# LED_Tweezer.net
KiCad netlist of a schematic drawn in Altium Designer
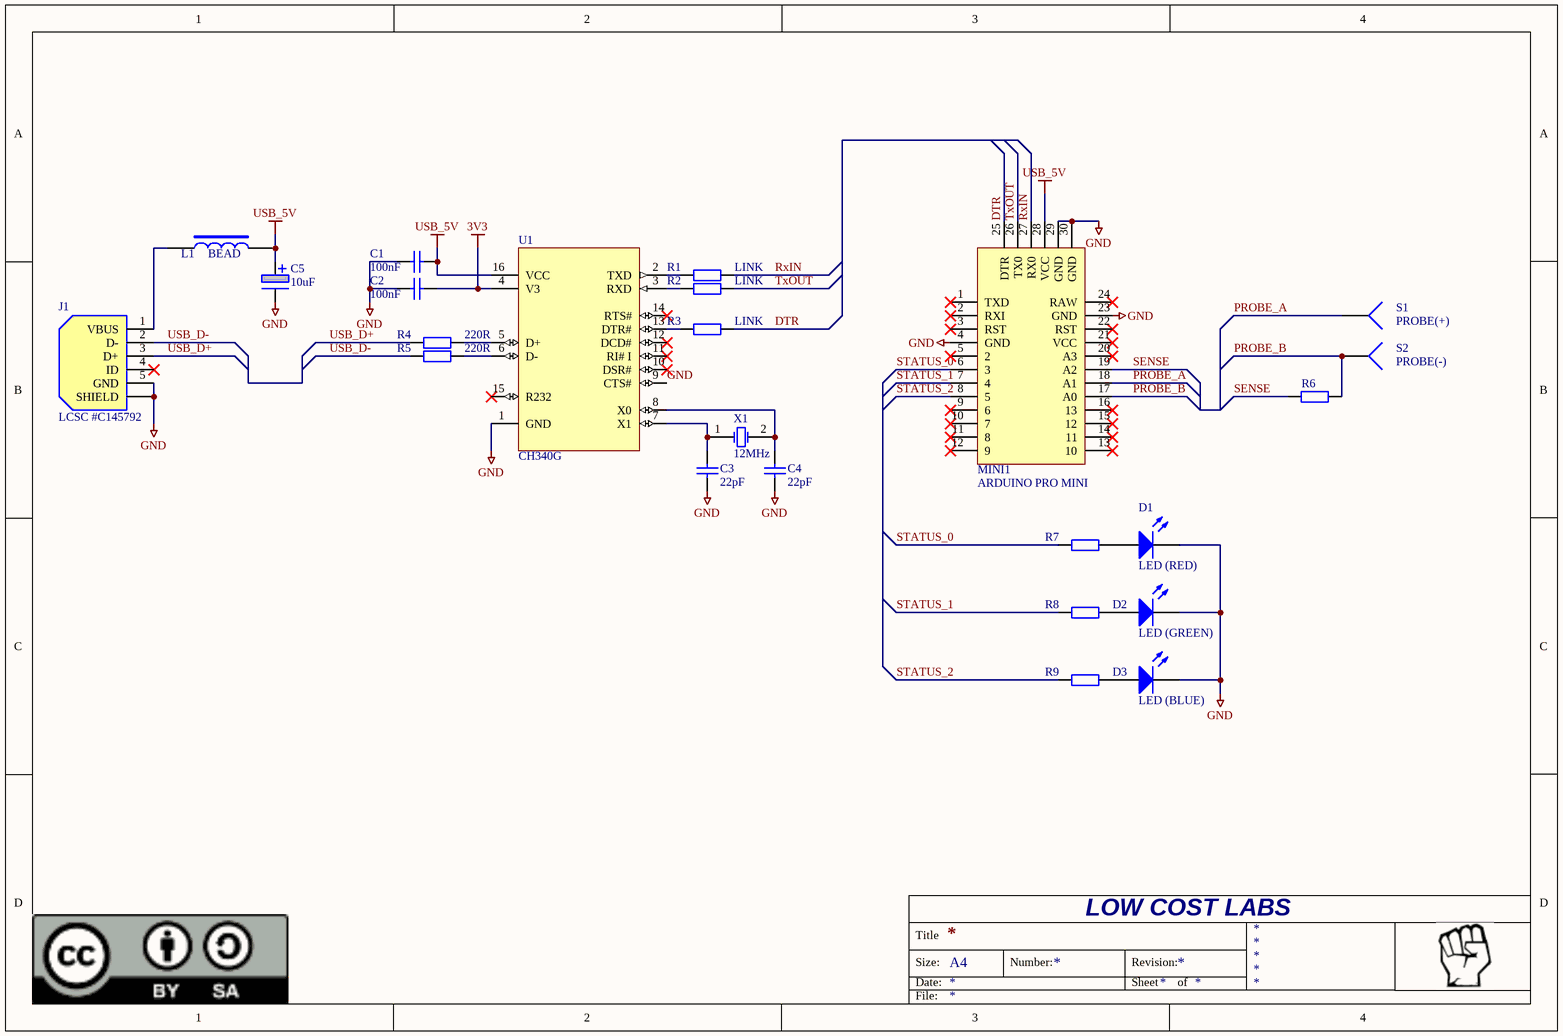
[diagram p0: LED Tweezer.SchDoc]

(export (version "E")
  (design (tool "Eeschema 10.0.6"))
  (components
    (comp (ref "C1")
      (value "100nF")
      (footprint "CAPACITOR 0805")
      (description "GENERIC 0603 CAPACITOR (IPCC COMPLIANT)")
      (libsource (lib "FavoritesLibrary") (part "SYM-xz5e0ntg24ede4ywr789-1"))
    )
    (comp (ref "C2")
      (value "100nF")
      (footprint "CAPACITOR 0805")
      (description "GENERIC 0603 CAPACITOR (IPCC COMPLIANT)")
      (libsource (lib "FavoritesLibrary") (part "SYM-xz5e0ntg24ede4ywr789-1"))
    )
    (comp (ref "C3")
      (value "22pF")
      (footprint "CAPACITOR 0805")
      (description "Capacitor 0805")
      (libsource (lib "altium-import") (part "root_3_SYM-xz5e0ntg24ede4ywr789-1_"))
    )
    (comp (ref "C4")
      (value "22pF")
      (footprint "CAPACITOR 0805")
      (description "Capacitor 0805")
      (libsource (lib "altium-import") (part "root_3_SYM-xz5e0ntg24ede4ywr789-1_"))
    )
    (comp (ref "C5")
      (value "10uF")
      (footprint "Simon Says:CAP ELECTRO 5mm")
      (description "5mm Through Hole Electrolytic 2mm Pitch, 5mm height")
      (libsource (lib "FavoritesLibrary") (part "SYM-su2zmkw1kc3z49ns9isd-1"))
    )
    (comp (ref "D1")
      (value "LED (RED)")
      (footprint "LED(3D) 3MM VERTICAL (GREEN)")
      (description "3mm RED LED")
      (fields (field (name "MOUSER PART NO.") "604-WP132XIT") (field (name "FARNELL PART NO.") "1003393"))
      (libsource (lib "NASCO") (part "LED 3mm RED"))
    )
    (comp (ref "D2")
      (value "LED (GREEN)")
      (footprint "LED(3D) 3MM VERTICAL (GREEN)")
      (description "3mm RED LED")
      (fields (field (name "MOUSER PART NO.") "604-WP132XIT") (field (name "FARNELL PART NO.") "1003393"))
      (libsource (lib "NASCO") (part "LED 3mm RED"))
    )
    (comp (ref "D3")
      (value "LED (BLUE)")
      (footprint "LED(3D) 3MM VERTICAL (GREEN)")
      (description "3mm RED LED")
      (fields (field (name "MOUSER PART NO.") "604-WP132XIT") (field (name "FARNELL PART NO.") "1003393"))
      (libsource (lib "NASCO") (part "LED 3mm RED"))
    )
    (comp (ref "J1")
      (value "LCSC #C145792")
      (footprint "MICRO-B-USB-SMD")
      (description "Hirose ZX62D-B-5PA8 MICRO USB")
      (fields (field (name "MANUFACTURER PART NUMBER") "ZX62D-B-5PA8"))
      (libsource (lib "altium-import") (part "root_0_HIRO-ZX62D-B_"))
    )
    (comp (ref "L1")
      (value "BEAD")
      (footprint "RES (3D) - 1210")
      (description "INDUCTOR SMD 1210")
      (fields (field (name "MOUSER PART NO.") "636-2512063007Y3") (field (name "MANUFACTURER") "Fair-Rite"))
      (libsource (lib "NASCO") (part "INDUCTOR SMD 1210 100uH"))
    )
    (comp (ref "MINI1")
      (value "ARDUINO PRO MINI")
      (footprint "ARDUINO PRO MINI")
      (libsource (lib "EletroSketch") (part "ARDUINO PRO MINI"))
    )
    (comp (ref "R1")
      (value "LINK")
      (footprint "RESISTOR 0805")
      (description "GENERIC 0603 RESISTOR (IPCC COMPLIANT)")
      (libsource (lib "altium-import") (part "root_0_SYM-nyzt47j077kuntqddeld-1_"))
    )
    (comp (ref "R2")
      (value "LINK")
      (footprint "RESISTOR 0805")
      (description "GENERIC 0603 RESISTOR (IPCC COMPLIANT)")
      (libsource (lib "altium-import") (part "root_0_SYM-nyzt47j077kuntqddeld-1_"))
    )
    (comp (ref "R3")
      (value "LINK")
      (footprint "RESISTOR 0805")
      (description "GENERIC 0603 RESISTOR (IPCC COMPLIANT)")
      (libsource (lib "altium-import") (part "root_0_SYM-nyzt47j077kuntqddeld-1_"))
    )
    (comp (ref "R4")
      (value "220R")
      (footprint "RESISTOR 0805")
      (description "GENERIC 0603 RESISTOR (IPCC COMPLIANT)")
      (libsource (lib "altium-import") (part "root_0_SYM-nyzt47j077kuntqddeld-1_"))
    )
    (comp (ref "R5")
      (value "220R")
      (footprint "RESISTOR 0805")
      (description "GENERIC 0603 RESISTOR (IPCC COMPLIANT)")
      (libsource (lib "altium-import") (part "root_0_SYM-nyzt47j077kuntqddeld-1_"))
    )
    (comp (ref "R6")
      (value "~")
      (footprint "RESISTOR 0805")
      (description "Resistor")
      (fields (field (name "PUBLISHER") "Altium Limited"))
      (libsource (lib "Miscellaneous Devices") (part "Res2"))
    )
    (comp (ref "R7")
      (value "~")
      (footprint "RESISTOR 0805")
      (description "Resistor")
      (fields (field (name "PUBLISHER") "Altium Limited"))
      (libsource (lib "Miscellaneous Devices") (part "Res2"))
    )
    (comp (ref "R8")
      (value "~")
      (footprint "RESISTOR 0805")
      (description "Resistor")
      (fields (field (name "PUBLISHER") "Altium Limited"))
      (libsource (lib "Miscellaneous Devices") (part "Res2"))
    )
    (comp (ref "R9")
      (value "~")
      (footprint "RESISTOR 0805")
      (description "Resistor")
      (fields (field (name "PUBLISHER") "Altium Limited"))
      (libsource (lib "") (part "Res2_1"))
    )
    (comp (ref "S1")
      (value "PROBE(+)")
      (footprint "SOCKET-SQUARE")
      (description "Banana Socket")
      (libsource (lib "Schlib1") (part "Banana Plug Socket"))
    )
    (comp (ref "S2")
      (value "PROBE(-)")
      (footprint "SOCKET-ROUND")
      (description "Banana Socket")
      (libsource (lib "Schlib1") (part "Banana Plug Socket"))
    )
    (comp (ref "U1")
      (value "CH340G")
      (footprint "SOIC-16")
      (description "CH340G USB To Serial (TTL) Module")
      (libsource (lib "Schlib1") (part "CH340G"))
    )
    (comp (ref "X1")
      (value "12MHz")
      (footprint "ABRA-AB15T-2_V")
      (libsource (lib "altium-import") (part "root_0_ABRA-XTAL_1-2-2_"))
    )
  )
  (nets
    (net (code "1") (name "/DTR") (class "Default")
      (node (ref "MINI1") (pin "25") (pinfunction "DTR_25") (pintype "passive"))
      (node (ref "R3") (pin "2") (pinfunction "2_2") (pintype "passive"))
    )
    (net (code "2") (name "/PROBE_A") (class "Default")
      (node (ref "MINI1") (pin "18") (pinfunction "A1_18") (pintype "passive"))
      (node (ref "S1") (pin "1") (pinfunction "1_1") (pintype "passive"))
    )
    (net (code "3") (name "/PROBE_B") (class "Default")
      (node (ref "MINI1") (pin "17") (pinfunction "A0_17") (pintype "passive"))
      (node (ref "R6") (pin "2") (pinfunction "2_2") (pintype "passive"))
      (node (ref "S2") (pin "1") (pinfunction "1_1") (pintype "passive"))
    )
    (net (code "4") (name "/RxIN") (class "Default")
      (node (ref "MINI1") (pin "27") (pinfunction "RX0_27") (pintype "passive"))
      (node (ref "R1") (pin "2") (pinfunction "2_2") (pintype "passive"))
    )
    (net (code "5") (name "/SENSE") (class "Default")
      (node (ref "MINI1") (pin "19") (pinfunction "A2_19") (pintype "passive"))
      (node (ref "R6") (pin "1") (pinfunction "1_1") (pintype "passive"))
    )
    (net (code "6") (name "/STATUS_0") (class "Default")
      (node (ref "MINI1") (pin "6") (pinfunction "3_6") (pintype "passive"))
      (node (ref "R7") (pin "1") (pinfunction "1_1") (pintype "passive"))
    )
    (net (code "7") (name "/STATUS_1") (class "Default")
      (node (ref "MINI1") (pin "7") (pinfunction "4_7") (pintype "passive"))
      (node (ref "R8") (pin "1") (pinfunction "1_1") (pintype "passive"))
    )
    (net (code "8") (name "/STATUS_2") (class "Default")
      (node (ref "MINI1") (pin "8") (pinfunction "5_8") (pintype "passive"))
      (node (ref "R9") (pin "2") (pinfunction "2_2") (pintype "passive"))
    )
    (net (code "9") (name "/TxOUT") (class "Default")
      (node (ref "MINI1") (pin "26") (pinfunction "TX0_26") (pintype "passive"))
      (node (ref "R2") (pin "2") (pinfunction "2_2") (pintype "passive"))
    )
    (net (code "10") (name "/USB_D+") (class "Default")
      (node (ref "J1") (pin "3") (pinfunction "D+_3") (pintype "passive"))
      (node (ref "R4") (pin "1") (pinfunction "1_1") (pintype "passive"))
    )
    (net (code "11") (name "/USB_D-") (class "Default")
      (node (ref "J1") (pin "2") (pinfunction "D-_2") (pintype "passive"))
      (node (ref "R5") (pin "1") (pinfunction "1_1") (pintype "passive"))
    )
    (net (code "12") (name "3V3") (class "Default")
      (node (ref "C2") (pin "1") (pinfunction "1_1") (pintype "passive"))
      (node (ref "U1") (pin "4") (pinfunction "V3_4") (pintype "power_in"))
    )
    (net (code "13") (name "GND") (class "Default")
      (node (ref "C1") (pin "2") (pinfunction "2_2") (pintype "passive"))
      (node (ref "C2") (pin "2") (pinfunction "2_2") (pintype "passive"))
      (node (ref "C3") (pin "2") (pinfunction "2_2") (pintype "passive"))
      (node (ref "C4") (pin "2") (pinfunction "2_2") (pintype "passive"))
      (node (ref "C5") (pin "2") (pinfunction "2_2") (pintype "passive"))
      (node (ref "D1") (pin "2") (pinfunction "K_2") (pintype "passive"))
      (node (ref "D2") (pin "2") (pinfunction "K_2") (pintype "passive"))
      (node (ref "D3") (pin "2") (pinfunction "K_2") (pintype "passive"))
      (node (ref "J1") (pin "5") (pinfunction "GND_5") (pintype "passive"))
      (node (ref "J1") (pin "SHIELD") (pinfunction "SHIELD_SHIELD") (pintype "passive"))
      (node (ref "MINI1") (pin "23") (pinfunction "GND_23") (pintype "passive"))
      (node (ref "MINI1") (pin "29") (pinfunction "GND_29") (pintype "passive"))
      (node (ref "MINI1") (pin "30") (pinfunction "GND_30") (pintype "passive"))
      (node (ref "MINI1") (pin "4") (pinfunction "GND_4") (pintype "passive"))
      (node (ref "U1") (pin "1") (pinfunction "GND_1") (pintype "power_in"))
      (node (ref "U1") (pin "9") (pinfunction "CTS#_9") (pintype "bidirectional"))
    )
    (net (code "14") (name "Net-(D1-A)") (class "Default")
      (node (ref "D1") (pin "1") (pinfunction "A_1") (pintype "passive"))
      (node (ref "R7") (pin "2") (pinfunction "2_2") (pintype "passive"))
    )
    (net (code "15") (name "Net-(D2-A)") (class "Default")
      (node (ref "D2") (pin "1") (pinfunction "A_1") (pintype "passive"))
      (node (ref "R8") (pin "2") (pinfunction "2_2") (pintype "passive"))
    )
    (net (code "16") (name "Net-(D3-A)") (class "Default")
      (node (ref "D3") (pin "1") (pinfunction "A_1") (pintype "passive"))
      (node (ref "R9") (pin "1") (pinfunction "1_1") (pintype "passive"))
    )
    (net (code "17") (name "Net-(J1-VBUS)") (class "Default")
      (node (ref "J1") (pin "1") (pinfunction "VBUS_1") (pintype "passive"))
      (node (ref "L1") (pin "1") (pinfunction "1_1") (pintype "passive"))
    )
    (net (code "18") (name "Net-(U1-D+)") (class "Default")
      (node (ref "R4") (pin "2") (pinfunction "2_2") (pintype "passive"))
      (node (ref "U1") (pin "5") (pinfunction "D+_5") (pintype "bidirectional"))
    )
    (net (code "19") (name "Net-(U1-D-)") (class "Default")
      (node (ref "R5") (pin "2") (pinfunction "2_2") (pintype "passive"))
      (node (ref "U1") (pin "6") (pinfunction "D-_6") (pintype "bidirectional"))
    )
    (net (code "20") (name "Net-(U1-DTR#)") (class "Default")
      (node (ref "R3") (pin "1") (pinfunction "1_1") (pintype "passive"))
      (node (ref "U1") (pin "13") (pinfunction "DTR#_13") (pintype "bidirectional"))
    )
    (net (code "21") (name "Net-(U1-RXD)") (class "Default")
      (node (ref "R2") (pin "1") (pinfunction "1_1") (pintype "passive"))
      (node (ref "U1") (pin "3") (pinfunction "RXD_3") (pintype "input"))
    )
    (net (code "22") (name "Net-(U1-TXD)") (class "Default")
      (node (ref "R1") (pin "1") (pinfunction "1_1") (pintype "passive"))
      (node (ref "U1") (pin "2") (pinfunction "TXD_2") (pintype "output"))
    )
    (net (code "23") (name "Net-(U1-X0)") (class "Default")
      (node (ref "C4") (pin "1") (pinfunction "1_1") (pintype "passive"))
      (node (ref "U1") (pin "8") (pinfunction "X0_8") (pintype "bidirectional"))
      (node (ref "X1") (pin "2") (pinfunction "X2_2") (pintype "passive"))
    )
    (net (code "24") (name "Net-(U1-X1)") (class "Default")
      (node (ref "C3") (pin "1") (pinfunction "1_1") (pintype "passive"))
      (node (ref "U1") (pin "7") (pinfunction "X1_7") (pintype "bidirectional"))
      (node (ref "X1") (pin "1") (pinfunction "X1_1") (pintype "passive"))
    )
    (net (code "25") (name "USB_5V") (class "Default")
      (node (ref "C1") (pin "1") (pinfunction "1_1") (pintype "passive"))
      (node (ref "C5") (pin "1") (pinfunction "1_1") (pintype "passive"))
      (node (ref "L1") (pin "2") (pinfunction "2_2") (pintype "passive"))
      (node (ref "MINI1") (pin "28") (pinfunction "VCC_28") (pintype "passive"))
      (node (ref "U1") (pin "16") (pinfunction "VCC_16") (pintype "power_in"))
    )
    (net (code "26") (name "unconnected-(J1-ID-Pad4)") (class "Default")
      (node (ref "J1") (pin "4") (pinfunction "ID_4") (pintype "passive+no_connect"))
    )
    (net (code "27") (name "unconnected-(MINI1-2-Pad5)") (class "Default")
      (node (ref "MINI1") (pin "5") (pinfunction "2_5") (pintype "passive+no_connect"))
    )
    (net (code "28") (name "unconnected-(MINI1-6-Pad9)") (class "Default")
      (node (ref "MINI1") (pin "9") (pinfunction "6_9") (pintype "passive+no_connect"))
    )
    (net (code "29") (name "unconnected-(MINI1-7-Pad10)") (class "Default")
      (node (ref "MINI1") (pin "10") (pinfunction "7_10") (pintype "passive+no_connect"))
    )
    (net (code "30") (name "unconnected-(MINI1-8-Pad11)") (class "Default")
      (node (ref "MINI1") (pin "11") (pinfunction "8_11") (pintype "passive+no_connect"))
    )
    (net (code "31") (name "unconnected-(MINI1-9-Pad12)") (class "Default")
      (node (ref "MINI1") (pin "12") (pinfunction "9_12") (pintype "passive+no_connect"))
    )
    (net (code "32") (name "unconnected-(MINI1-10-Pad13)") (class "Default")
      (node (ref "MINI1") (pin "13") (pinfunction "10_13") (pintype "passive+no_connect"))
    )
    (net (code "33") (name "unconnected-(MINI1-11-Pad14)") (class "Default")
      (node (ref "MINI1") (pin "14") (pinfunction "11_14") (pintype "passive+no_connect"))
    )
    (net (code "34") (name "unconnected-(MINI1-12-Pad15)") (class "Default")
      (node (ref "MINI1") (pin "15") (pinfunction "12_15") (pintype "passive+no_connect"))
    )
    (net (code "35") (name "unconnected-(MINI1-13-Pad16)") (class "Default")
      (node (ref "MINI1") (pin "16") (pinfunction "13_16") (pintype "passive+no_connect"))
    )
    (net (code "36") (name "unconnected-(MINI1-A3-Pad20)") (class "Default")
      (node (ref "MINI1") (pin "20") (pinfunction "A3_20") (pintype "passive+no_connect"))
    )
    (net (code "37") (name "unconnected-(MINI1-RAW-Pad24)") (class "Default")
      (node (ref "MINI1") (pin "24") (pinfunction "RAW_24") (pintype "passive+no_connect"))
    )
    (net (code "38") (name "unconnected-(MINI1-RST-Pad3)") (class "Default")
      (node (ref "MINI1") (pin "3") (pinfunction "RST_3") (pintype "passive+no_connect"))
    )
    (net (code "39") (name "unconnected-(MINI1-RST-Pad22)") (class "Default")
      (node (ref "MINI1") (pin "22") (pinfunction "RST_22") (pintype "passive+no_connect"))
    )
    (net (code "40") (name "unconnected-(MINI1-RXI-Pad2)") (class "Default")
      (node (ref "MINI1") (pin "2") (pinfunction "RXI_2") (pintype "passive+no_connect"))
    )
    (net (code "41") (name "unconnected-(MINI1-TXD-Pad1)") (class "Default")
      (node (ref "MINI1") (pin "1") (pinfunction "TXD_1") (pintype "passive+no_connect"))
    )
    (net (code "42") (name "unconnected-(MINI1-VCC-Pad21)") (class "Default")
      (node (ref "MINI1") (pin "21") (pinfunction "VCC_21") (pintype "passive+no_connect"))
    )
    (net (code "43") (name "unconnected-(U1-DCD#-Pad12)") (class "Default")
      (node (ref "U1") (pin "12") (pinfunction "DCD#_12") (pintype "bidirectional+no_connect"))
    )
    (net (code "44") (name "unconnected-(U1-DSR#-Pad10)") (class "Default")
      (node (ref "U1") (pin "10") (pinfunction "DSR#_10") (pintype "bidirectional+no_connect"))
    )
    (net (code "45") (name "unconnected-(U1-R232-Pad15)") (class "Default")
      (node (ref "U1") (pin "15") (pinfunction "R232_15") (pintype "bidirectional+no_connect"))
    )
    (net (code "46") (name "unconnected-(U1-RI#_I-Pad11)") (class "Default")
      (node (ref "U1") (pin "11") (pinfunction "RI#_I_11") (pintype "bidirectional+no_connect"))
    )
    (net (code "47") (name "unconnected-(U1-RTS#-Pad14)") (class "Default")
      (node (ref "U1") (pin "14") (pinfunction "RTS#_14") (pintype "bidirectional+no_connect"))
    )
  )
)
